# Sheet2.net
KiCad netlist of a schematic drawn in Altium Designer
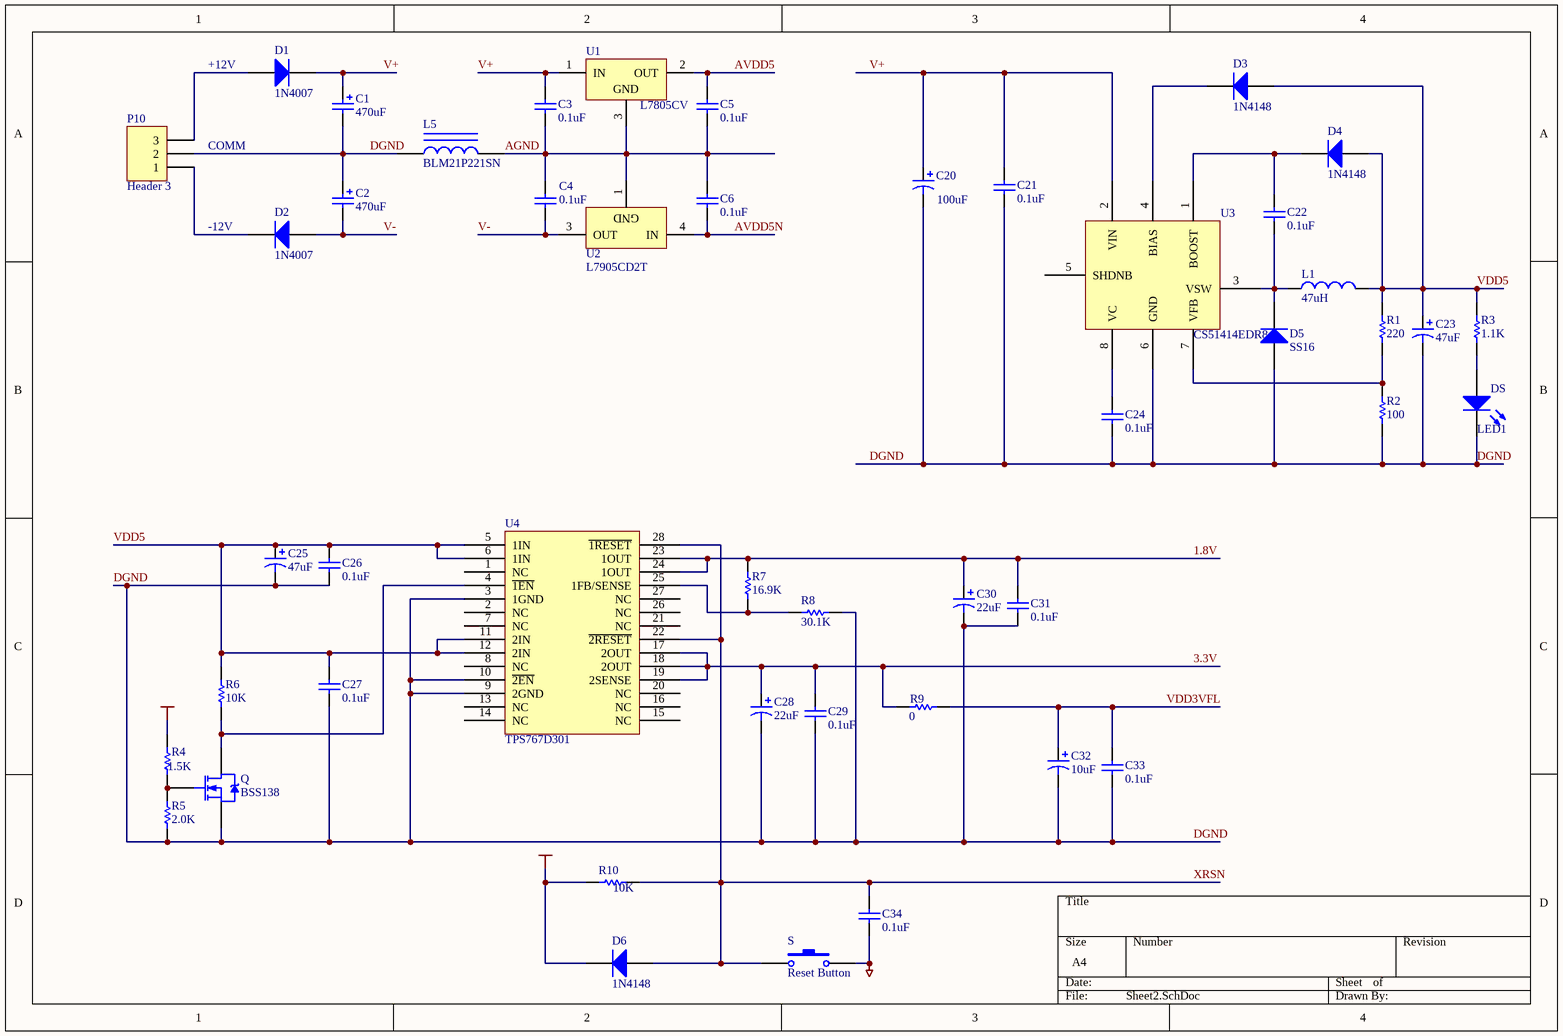
[diagram p0: Sheet2.SchDoc]

(export (version "E")
  (design (tool "Eeschema 10.0.6"))
  (components
    (comp (ref "C1")
      (value "470uF")
      (footprint "C0915-0508")
      (description "Polarized Capacitor (Axial)")
      (fields (field (name "PUBLISHER") "Altium Limited"))
      (libsource (lib "Miscellaneous Devices") (part "Cap Pol2"))
    )
    (comp (ref "C2")
      (value "470uF")
      (footprint "C0915-0508")
      (description "Polarized Capacitor (Axial)")
      (fields (field (name "PUBLISHER") "Altium Limited"))
      (libsource (lib "Miscellaneous Devices") (part "Cap Pol2"))
    )
    (comp (ref "C3")
      (value "0.1uF")
      (footprint "CC2012-0805")
      (description "Capacitor (Semiconductor SIM Model)")
      (fields (field (name "PUBLISHER") "Altium Limited"))
      (libsource (lib "Miscellaneous Devices") (part "Cap Semi"))
    )
    (comp (ref "C4")
      (value "0.1uF")
      (footprint "CC2012-0805")
      (description "Capacitor (Semiconductor SIM Model)")
      (fields (field (name "PUBLISHER") "Altium Limited"))
      (libsource (lib "Miscellaneous Devices") (part "Cap Semi"))
    )
    (comp (ref "C5")
      (value "0.1uF")
      (footprint "CC2012-0805")
      (description "Capacitor (Semiconductor SIM Model)")
      (fields (field (name "PUBLISHER") "Altium Limited"))
      (libsource (lib "Miscellaneous Devices") (part "Cap Semi"))
    )
    (comp (ref "C6")
      (value "0.1uF")
      (footprint "CC2012-0805")
      (description "Capacitor (Semiconductor SIM Model)")
      (fields (field (name "PUBLISHER") "Altium Limited"))
      (libsource (lib "Miscellaneous Devices") (part "Cap Semi"))
    )
    (comp (ref "C20")
      (value "100uF")
      (footprint "C0915-0350")
      (description "Polarized Capacitor (Radial)")
      (fields (field (name "PUBLISHER") "Altium Limited"))
      (libsource (lib "Miscellaneous Devices") (part "Cap Pol1"))
    )
    (comp (ref "C21")
      (value "0.1uF")
      (footprint "CC2012-0805")
      (description "Capacitor")
      (fields (field (name "PUBLISHER") "Altium Limited"))
      (libsource (lib "Miscellaneous Devices") (part "Cap"))
    )
    (comp (ref "C22")
      (value "0.1uF")
      (footprint "CC2012-0805")
      (description "Capacitor")
      (fields (field (name "PUBLISHER") "Altium Limited"))
      (libsource (lib "Miscellaneous Devices") (part "Cap"))
    )
    (comp (ref "C23")
      (value "47uF")
      (footprint "CA2522-0612")
      (description "Polarized Capacitor (Radial)")
      (fields (field (name "PUBLISHER") "Altium Limited"))
      (libsource (lib "Miscellaneous Devices") (part "Cap Pol1"))
    )
    (comp (ref "C24")
      (value "0.1uF")
      (footprint "CC2012-0805")
      (description "Capacitor")
      (fields (field (name "PUBLISHER") "Altium Limited"))
      (libsource (lib "Miscellaneous Devices") (part "Cap"))
    )
    (comp (ref "C25")
      (value "47uF")
      (footprint "CA2522-0612")
      (description "Polarized Capacitor (Radial)")
      (fields (field (name "PUBLISHER") "Altium Limited"))
      (libsource (lib "Miscellaneous Devices") (part "Cap Pol1"))
    )
    (comp (ref "C26")
      (value "0.1uF")
      (footprint "CC2012-0805")
      (description "Capacitor")
      (fields (field (name "PUBLISHER") "Altium Limited"))
      (libsource (lib "Miscellaneous Devices") (part "Cap"))
    )
    (comp (ref "C27")
      (value "0.1uF")
      (footprint "CC2012-0805")
      (description "Capacitor")
      (fields (field (name "PUBLISHER") "Altium Limited"))
      (libsource (lib "Miscellaneous Devices") (part "Cap"))
    )
    (comp (ref "C28")
      (value "22uF")
      (footprint "CA2222-0350")
      (description "Polarized Capacitor (Radial)")
      (fields (field (name "PUBLISHER") "Altium Limited"))
      (libsource (lib "Miscellaneous Devices") (part "Cap Pol1"))
    )
    (comp (ref "C29")
      (value "0.1uF")
      (footprint "CC2012-0805")
      (description "Capacitor")
      (fields (field (name "PUBLISHER") "Altium Limited"))
      (libsource (lib "Miscellaneous Devices") (part "Cap"))
    )
    (comp (ref "C30")
      (value "22uF")
      (footprint "CA2222-0350")
      (description "Polarized Capacitor (Radial)")
      (fields (field (name "PUBLISHER") "Altium Limited"))
      (libsource (lib "Miscellaneous Devices") (part "Cap Pol1"))
    )
    (comp (ref "C31")
      (value "0.1uF")
      (footprint "CC2012-0805")
      (description "Capacitor")
      (fields (field (name "PUBLISHER") "Altium Limited"))
      (libsource (lib "Miscellaneous Devices") (part "Cap"))
    )
    (comp (ref "C32")
      (value "10uF")
      (footprint "CA2222-0370")
      (description "Polarized Capacitor (Surface Mount)")
      (fields (field (name "PUBLISHER") "Altium Limited"))
      (libsource (lib "Miscellaneous Devices") (part "Cap Pol3"))
    )
    (comp (ref "C33")
      (value "0.1uF")
      (footprint "CC2012-0805")
      (description "Capacitor")
      (fields (field (name "PUBLISHER") "Altium Limited"))
      (libsource (lib "Miscellaneous Devices") (part "Cap"))
    )
    (comp (ref "C34")
      (value "0.1uF")
      (footprint "CC2012-0805")
      (description "Capacitor")
      (fields (field (name "PUBLISHER") "Altium Limited"))
      (libsource (lib "Miscellaneous Devices") (part "Cap"))
    )
    (comp (ref "D1")
      (value "1N4007")
      (footprint "DO-41")
      (description "1.0 Ampere General Purpose Rectifier")
      (fields (field (name "PUBLISHER") "Altium Limited"))
      (libsource (lib "FSC Discrete Rectifier") (part "1N4007"))
    )
    (comp (ref "D2")
      (value "1N4007")
      (footprint "DO-41")
      (description "1.0 Ampere General Purpose Rectifier")
      (fields (field (name "PUBLISHER") "Altium Limited"))
      (libsource (lib "FSC Discrete Rectifier") (part "1N4007"))
    )
    (comp (ref "D3")
      (value "1N4148")
      (footprint "D2012-0350")
      (description "High Conductance Fast Diode")
      (fields (field (name "PUBLISHER") "Altium Limited"))
      (libsource (lib "Miscellaneous Devices") (part "Diode 1N4148"))
    )
    (comp (ref "D4")
      (value "1N4148")
      (footprint "D2012-0350")
      (description "High Conductance Fast Diode")
      (fields (field (name "PUBLISHER") "Altium Limited"))
      (libsource (lib "Miscellaneous Devices") (part "Diode 1N4148"))
    )
    (comp (ref "D5")
      (value "SS16")
      (footprint "D2220-0500")
      (description "Default Diode")
      (fields (field (name "PUBLISHER") "Altium Limited"))
      (libsource (lib "Miscellaneous Devices") (part "Diode"))
    )
    (comp (ref "D6")
      (value "1N4148")
      (footprint "D2012-0350")
      (description "High Conductance Fast Diode")
      (fields (field (name "PUBLISHER") "Altium Limited"))
      (libsource (lib "Miscellaneous Devices") (part "Diode 1N4148"))
    )
    (comp (ref "DS")
      (value "LED1")
      (footprint "LED-1")
      (description "Typical RED GaAs LED")
      (fields (field (name "PUBLISHER") "Altium Limited"))
      (libsource (lib "Miscellaneous Devices") (part "LED1"))
    )
    (comp (ref "L1")
      (value "47uH")
      (footprint "L2025-0712")
      (description "Inductor")
      (fields (field (name "PUBLISHER") "Altium Limited"))
      (libsource (lib "Miscellaneous Devices") (part "Inductor"))
    )
    (comp (ref "L5")
      (value "BLM21P221SN")
      (footprint "CR2012-0805")
      (description "Magnetic-Core Inductor")
      (fields (field (name "PUBLISHER") "Altium Limited"))
      (libsource (lib "Miscellaneous Devices") (part "Inductor Iron"))
    )
    (comp (ref "P10")
      (value "Header 3")
      (footprint "HEADER3")
      (description "Header, 3-Pin")
      (fields (field (name "PUBLISHER") "Altium Limited"))
      (libsource (lib "Miscellaneous Connectors") (part "Header 3"))
    )
    (comp (ref "Q") (value "BSS138") (footprint "SO-G3/Z3.3") (libsource (lib "MyIntLib") (part "BSS138")))
    (comp (ref "R1")
      (value "220")
      (footprint "CR2012-0805")
      (description "Resistor")
      (fields (field (name "PUBLISHER") "Altium Limited"))
      (libsource (lib "Miscellaneous Devices") (part "Res1"))
    )
    (comp (ref "R2")
      (value "100")
      (footprint "CR2012-0805")
      (description "Resistor")
      (fields (field (name "PUBLISHER") "Altium Limited"))
      (libsource (lib "Miscellaneous Devices") (part "Res1"))
    )
    (comp (ref "R3")
      (value "1.1K")
      (footprint "CR2012-0805")
      (description "Resistor")
      (fields (field (name "PUBLISHER") "Altium Limited"))
      (libsource (lib "Miscellaneous Devices") (part "Res1"))
    )
    (comp (ref "R4")
      (value "1.5K")
      (footprint "CR2012-0805")
      (description "Resistor")
      (fields (field (name "PUBLISHER") "Altium Limited"))
      (libsource (lib "Miscellaneous Devices") (part "Res1"))
    )
    (comp (ref "R5")
      (value "2.0K")
      (footprint "CR2012-0805")
      (description "Resistor")
      (fields (field (name "PUBLISHER") "Altium Limited"))
      (libsource (lib "Miscellaneous Devices") (part "Res1"))
    )
    (comp (ref "R6")
      (value "10K")
      (footprint "CR2012-0805")
      (description "Resistor")
      (fields (field (name "PUBLISHER") "Altium Limited"))
      (libsource (lib "Miscellaneous Devices") (part "Res1"))
    )
    (comp (ref "R7")
      (value "16.9K")
      (footprint "CR2012-0805")
      (description "Resistor")
      (fields (field (name "PUBLISHER") "Altium Limited"))
      (libsource (lib "Miscellaneous Devices") (part "Res1"))
    )
    (comp (ref "R8")
      (value "30.1K")
      (footprint "CR2012-0805")
      (description "Resistor")
      (fields (field (name "PUBLISHER") "Altium Limited"))
      (libsource (lib "Miscellaneous Devices") (part "Res1"))
    )
    (comp (ref "R9")
      (value "0")
      (footprint "CR2012-0805")
      (description "Resistor")
      (fields (field (name "PUBLISHER") "Altium Limited"))
      (libsource (lib "Miscellaneous Devices") (part "Res1"))
    )
    (comp (ref "R10")
      (value "10K")
      (footprint "CR2012-0805")
      (description "Resistor")
      (fields (field (name "PUBLISHER") "Altium Limited"))
      (libsource (lib "Miscellaneous Devices") (part "Res1"))
    )
    (comp (ref "S")
      (value "Reset Button")
      (footprint "SW0915-4666")
      (description "Switch")
      (fields (field (name "PUBLISHER") "Altium Limited"))
      (libsource (lib "Miscellaneous Devices") (part "SW-PB"))
    )
    (comp (ref "U1")
      (value "L7805CV")
      (footprint "TO220ABN")
      (description "Positive Voltage Regulator")
      (fields (field (name "PUBLISHER") "Altium Limited"))
      (libsource (lib "ST Power Mgt Voltage Regulator") (part "L7805CV"))
    )
    (comp (ref "U2")
      (value "L7905CD2T")
      (footprint "TO-263")
      (description "Negative Voltage Regulator")
      (fields (field (name "PUBLISHER") "Altium Limited"))
      (libsource (lib "ST Power Mgt Voltage Regulator") (part "L7905CD2T"))
    )
    (comp (ref "U3")
      (value "CS51414EDR8")
      (footprint "AD8021ARZ-1")
      (libsource (lib "MyIntLib") (part "CS51414"))
    )
    (comp (ref "U4")
      (value "TPS767D301")
      (footprint "TPS767D301")
      (libsource (lib "MyIntLib") (part "TPS767D301"))
    )
  )
  (nets
    (net (code "1") (name "/1.8V") (class "Default")
      (node (ref "C30") (pin "1") (pinfunction "1_1") (pintype "passive"))
      (node (ref "C31") (pin "1") (pinfunction "1_1") (pintype "passive"))
      (node (ref "R7") (pin "2") (pinfunction "2_2") (pintype "passive"))
      (node (ref "U4") (pin "23") (pinfunction "1OUT_23") (pintype "passive"))
      (node (ref "U4") (pin "24") (pinfunction "1OUT_24") (pintype "passive"))
    )
    (net (code "2") (name "/AGND") (class "Default")
      (node (ref "C3") (pin "1") (pinfunction "1_1") (pintype "passive"))
      (node (ref "C4") (pin "2") (pinfunction "2_2") (pintype "passive"))
      (node (ref "C5") (pin "1") (pinfunction "1_1") (pintype "passive"))
      (node (ref "C6") (pin "1") (pinfunction "1_1") (pintype "passive"))
      (node (ref "L5") (pin "2") (pinfunction "2_2") (pintype "passive"))
      (node (ref "U1") (pin "3") (pinfunction "GND_3") (pintype "power_in"))
      (node (ref "U2") (pin "1") (pinfunction "GND_1") (pintype "power_in"))
    )
    (net (code "3") (name "/AVDD5") (class "Default")
      (node (ref "C5") (pin "2") (pinfunction "2_2") (pintype "passive"))
      (node (ref "U1") (pin "2") (pinfunction "OUT_2") (pintype "power_in"))
    )
    (net (code "4") (name "/AVDD5N") (class "Default")
      (node (ref "C6") (pin "2") (pinfunction "2_2") (pintype "passive"))
      (node (ref "U2") (pin "4") (pinfunction "IN_4") (pintype "power_in"))
    )
    (net (code "5") (name "/V+") (class "Default")
      (node (ref "C1") (pin "1") (pinfunction "1_1") (pintype "passive"))
      (node (ref "C20") (pin "1") (pinfunction "1_1") (pintype "passive"))
      (node (ref "C21") (pin "2") (pinfunction "2_2") (pintype "passive"))
      (node (ref "C3") (pin "2") (pinfunction "2_2") (pintype "passive"))
      (node (ref "D1") (pin "2") (pinfunction "K_2") (pintype "passive"))
      (node (ref "U1") (pin "1") (pinfunction "IN_1") (pintype "power_in"))
      (node (ref "U3") (pin "2") (pinfunction "VIN_2") (pintype "passive"))
    )
    (net (code "6") (name "/V-") (class "Default")
      (node (ref "C2") (pin "2") (pinfunction "2_2") (pintype "passive"))
      (node (ref "C4") (pin "1") (pinfunction "1_1") (pintype "passive"))
      (node (ref "D2") (pin "1") (pinfunction "A_1") (pintype "passive"))
      (node (ref "U2") (pin "3") (pinfunction "OUT_3") (pintype "power_in"))
    )
    (net (code "7") (name "/VDD3VFL") (class "Default")
      (node (ref "C32") (pin "1") (pinfunction "1_1") (pintype "passive"))
      (node (ref "C33") (pin "2") (pinfunction "2_2") (pintype "passive"))
      (node (ref "R9") (pin "2") (pinfunction "2_2") (pintype "passive"))
    )
    (net (code "8") (name "/VDD5") (class "Default")
      (node (ref "C23") (pin "1") (pinfunction "1_1") (pintype "passive"))
      (node (ref "C25") (pin "1") (pinfunction "1_1") (pintype "passive"))
      (node (ref "C26") (pin "2") (pinfunction "2_2") (pintype "passive"))
      (node (ref "C27") (pin "2") (pinfunction "2_2") (pintype "passive"))
      (node (ref "D3") (pin "1") (pinfunction "A_1") (pintype "passive"))
      (node (ref "D4") (pin "1") (pinfunction "A_1") (pintype "passive"))
      (node (ref "L1") (pin "2") (pinfunction "2_2") (pintype "passive"))
      (node (ref "R1") (pin "2") (pinfunction "2_2") (pintype "passive"))
      (node (ref "R3") (pin "2") (pinfunction "2_2") (pintype "passive"))
      (node (ref "R6") (pin "2") (pinfunction "2_2") (pintype "passive"))
      (node (ref "U4") (pin "11") (pinfunction "2IN_11") (pintype "passive"))
      (node (ref "U4") (pin "12") (pinfunction "2IN_12") (pintype "passive"))
      (node (ref "U4") (pin "5") (pinfunction "1IN_5") (pintype "passive"))
      (node (ref "U4") (pin "6") (pinfunction "1IN_6") (pintype "passive"))
    )
    (net (code "9") (name "/XRSN") (class "Default")
      (node (ref "C34") (pin "2") (pinfunction "2_2") (pintype "passive"))
      (node (ref "D6") (pin "1") (pinfunction "A_1") (pintype "passive"))
      (node (ref "R10") (pin "2") (pinfunction "2_2") (pintype "passive"))
      (node (ref "S") (pin "1") (pinfunction "1_1") (pintype "passive"))
      (node (ref "U4") (pin "22") (pinfunction "~{2RESET}_22") (pintype "passive"))
      (node (ref "U4") (pin "28") (pinfunction "~{1RESET}_28") (pintype "passive"))
    )
    (net (code "10") (name "3.3V") (class "Default")
      (node (ref "C28") (pin "1") (pinfunction "1_1") (pintype "passive"))
      (node (ref "C29") (pin "2") (pinfunction "2_2") (pintype "passive"))
      (node (ref "D6") (pin "2") (pinfunction "K_2") (pintype "passive"))
      (node (ref "R10") (pin "1") (pinfunction "1_1") (pintype "passive"))
      (node (ref "R4") (pin "2") (pinfunction "2_2") (pintype "passive"))
      (node (ref "R9") (pin "1") (pinfunction "1_1") (pintype "passive"))
      (node (ref "U4") (pin "17") (pinfunction "2OUT_17") (pintype "passive"))
      (node (ref "U4") (pin "18") (pinfunction "2OUT_18") (pintype "passive"))
      (node (ref "U4") (pin "19") (pinfunction "2SENSE_19") (pintype "passive"))
    )
    (net (code "11") (name "DGND") (class "Default")
      (node (ref "C1") (pin "2") (pinfunction "2_2") (pintype "passive"))
      (node (ref "C2") (pin "1") (pinfunction "1_1") (pintype "passive"))
      (node (ref "C20") (pin "2") (pinfunction "2_2") (pintype "passive"))
      (node (ref "C21") (pin "1") (pinfunction "1_1") (pintype "passive"))
      (node (ref "C23") (pin "2") (pinfunction "2_2") (pintype "passive"))
      (node (ref "C24") (pin "1") (pinfunction "1_1") (pintype "passive"))
      (node (ref "C25") (pin "2") (pinfunction "2_2") (pintype "passive"))
      (node (ref "C26") (pin "1") (pinfunction "1_1") (pintype "passive"))
      (node (ref "C27") (pin "1") (pinfunction "1_1") (pintype "passive"))
      (node (ref "C28") (pin "2") (pinfunction "2_2") (pintype "passive"))
      (node (ref "C29") (pin "1") (pinfunction "1_1") (pintype "passive"))
      (node (ref "C30") (pin "2") (pinfunction "2_2") (pintype "passive"))
      (node (ref "C31") (pin "2") (pinfunction "2_2") (pintype "passive"))
      (node (ref "C32") (pin "2") (pinfunction "2_2") (pintype "passive"))
      (node (ref "C33") (pin "1") (pinfunction "1_1") (pintype "passive"))
      (node (ref "C34") (pin "1") (pinfunction "1_1") (pintype "passive"))
      (node (ref "D5") (pin "1") (pinfunction "A_1") (pintype "passive"))
      (node (ref "DS") (pin "2") (pinfunction "K_2") (pintype "passive"))
      (node (ref "L5") (pin "1") (pinfunction "1_1") (pintype "passive"))
      (node (ref "P10") (pin "2") (pinfunction "2_2") (pintype "passive"))
      (node (ref "Q") (pin "2") (pinfunction "S_2") (pintype "passive"))
      (node (ref "R2") (pin "1") (pinfunction "1_1") (pintype "passive"))
      (node (ref "R5") (pin "1") (pinfunction "1_1") (pintype "passive"))
      (node (ref "R8") (pin "2") (pinfunction "2_2") (pintype "passive"))
      (node (ref "S") (pin "2") (pinfunction "2_2") (pintype "passive"))
      (node (ref "U3") (pin "6") (pinfunction "GND_6") (pintype "passive"))
      (node (ref "U4") (pin "10") (pinfunction "~{2EN}_10") (pintype "passive"))
      (node (ref "U4") (pin "3") (pinfunction "1GND_3") (pintype "passive"))
      (node (ref "U4") (pin "9") (pinfunction "2GND_9") (pintype "passive"))
    )
    (net (code "12") (name "Net-(D1-A)") (class "Default")
      (node (ref "D1") (pin "1") (pinfunction "A_1") (pintype "passive"))
      (node (ref "P10") (pin "3") (pinfunction "3_3") (pintype "passive"))
    )
    (net (code "13") (name "Net-(D2-K)") (class "Default")
      (node (ref "D2") (pin "2") (pinfunction "K_2") (pintype "passive"))
      (node (ref "P10") (pin "1") (pinfunction "1_1") (pintype "passive"))
    )
    (net (code "14") (name "Net-(D3-K)") (class "Default")
      (node (ref "D3") (pin "2") (pinfunction "K_2") (pintype "passive"))
      (node (ref "U3") (pin "4") (pinfunction "BIAS_4") (pintype "passive"))
    )
    (net (code "15") (name "Net-(D4-K)") (class "Default")
      (node (ref "C22") (pin "2") (pinfunction "2_2") (pintype "passive"))
      (node (ref "D4") (pin "2") (pinfunction "K_2") (pintype "passive"))
      (node (ref "U3") (pin "1") (pinfunction "BOOST_1") (pintype "passive"))
    )
    (net (code "16") (name "Net-(D5-K)") (class "Default")
      (node (ref "C22") (pin "1") (pinfunction "1_1") (pintype "passive"))
      (node (ref "D5") (pin "2") (pinfunction "K_2") (pintype "passive"))
      (node (ref "L1") (pin "1") (pinfunction "1_1") (pintype "passive"))
      (node (ref "U3") (pin "3") (pinfunction "VSW_3") (pintype "passive"))
    )
    (net (code "17") (name "Net-(DS-A)") (class "Default")
      (node (ref "DS") (pin "1") (pinfunction "A_1") (pintype "passive"))
      (node (ref "R3") (pin "1") (pinfunction "1_1") (pintype "passive"))
    )
    (net (code "18") (name "Net-(Q-D)") (class "Default")
      (node (ref "Q") (pin "3") (pinfunction "D_3") (pintype "passive"))
      (node (ref "R6") (pin "1") (pinfunction "1_1") (pintype "passive"))
      (node (ref "U4") (pin "4") (pinfunction "~{1EN}_4") (pintype "passive"))
    )
    (net (code "19") (name "Net-(Q-G)") (class "Default")
      (node (ref "Q") (pin "1") (pinfunction "G_1") (pintype "passive"))
      (node (ref "R4") (pin "1") (pinfunction "1_1") (pintype "passive"))
      (node (ref "R5") (pin "2") (pinfunction "2_2") (pintype "passive"))
    )
    (net (code "20") (name "Net-(U3-VC)") (class "Default")
      (node (ref "C24") (pin "2") (pinfunction "2_2") (pintype "passive"))
      (node (ref "U3") (pin "8") (pinfunction "VC_8") (pintype "passive"))
    )
    (net (code "21") (name "Net-(U3-VFB)") (class "Default")
      (node (ref "R1") (pin "1") (pinfunction "1_1") (pintype "passive"))
      (node (ref "R2") (pin "2") (pinfunction "2_2") (pintype "passive"))
      (node (ref "U3") (pin "7") (pinfunction "VFB_7") (pintype "passive"))
    )
    (net (code "22") (name "Net-(U4-1FB{slash}SENSE)") (class "Default")
      (node (ref "R7") (pin "1") (pinfunction "1_1") (pintype "passive"))
      (node (ref "R8") (pin "1") (pinfunction "1_1") (pintype "passive"))
      (node (ref "U4") (pin "25") (pinfunction "1FB/SENSE_25") (pintype "passive"))
    )
    (net (code "23") (name "unconnected-(U3-SHDNB-Pad5)") (class "Default")
      (node (ref "U3") (pin "5") (pinfunction "SHDNB_5") (pintype "passive"))
    )
    (net (code "24") (name "unconnected-(U4-NC-Pad1)") (class "Default")
      (node (ref "U4") (pin "1") (pinfunction "NC_1") (pintype "passive"))
    )
    (net (code "25") (name "unconnected-(U4-NC-Pad2)") (class "Default")
      (node (ref "U4") (pin "2") (pinfunction "NC_2") (pintype "passive"))
    )
    (net (code "26") (name "unconnected-(U4-NC-Pad7)") (class "Default")
      (node (ref "U4") (pin "7") (pinfunction "NC_7") (pintype "passive"))
    )
    (net (code "27") (name "unconnected-(U4-NC-Pad8)") (class "Default")
      (node (ref "U4") (pin "8") (pinfunction "NC_8") (pintype "passive"))
    )
    (net (code "28") (name "unconnected-(U4-NC-Pad13)") (class "Default")
      (node (ref "U4") (pin "13") (pinfunction "NC_13") (pintype "passive"))
    )
    (net (code "29") (name "unconnected-(U4-NC-Pad14)") (class "Default")
      (node (ref "U4") (pin "14") (pinfunction "NC_14") (pintype "passive"))
    )
    (net (code "30") (name "unconnected-(U4-NC-Pad15)") (class "Default")
      (node (ref "U4") (pin "15") (pinfunction "NC_15") (pintype "passive"))
    )
    (net (code "31") (name "unconnected-(U4-NC-Pad16)") (class "Default")
      (node (ref "U4") (pin "16") (pinfunction "NC_16") (pintype "passive"))
    )
    (net (code "32") (name "unconnected-(U4-NC-Pad20)") (class "Default")
      (node (ref "U4") (pin "20") (pinfunction "NC_20") (pintype "passive"))
    )
    (net (code "33") (name "unconnected-(U4-NC-Pad21)") (class "Default")
      (node (ref "U4") (pin "21") (pinfunction "NC_21") (pintype "passive"))
    )
    (net (code "34") (name "unconnected-(U4-NC-Pad26)") (class "Default")
      (node (ref "U4") (pin "26") (pinfunction "NC_26") (pintype "passive"))
    )
    (net (code "35") (name "unconnected-(U4-NC-Pad27)") (class "Default")
      (node (ref "U4") (pin "27") (pinfunction "NC_27") (pintype "passive"))
    )
  )
)
